# JTAG.net
KiCad netlist of a schematic drawn in Altium Designer
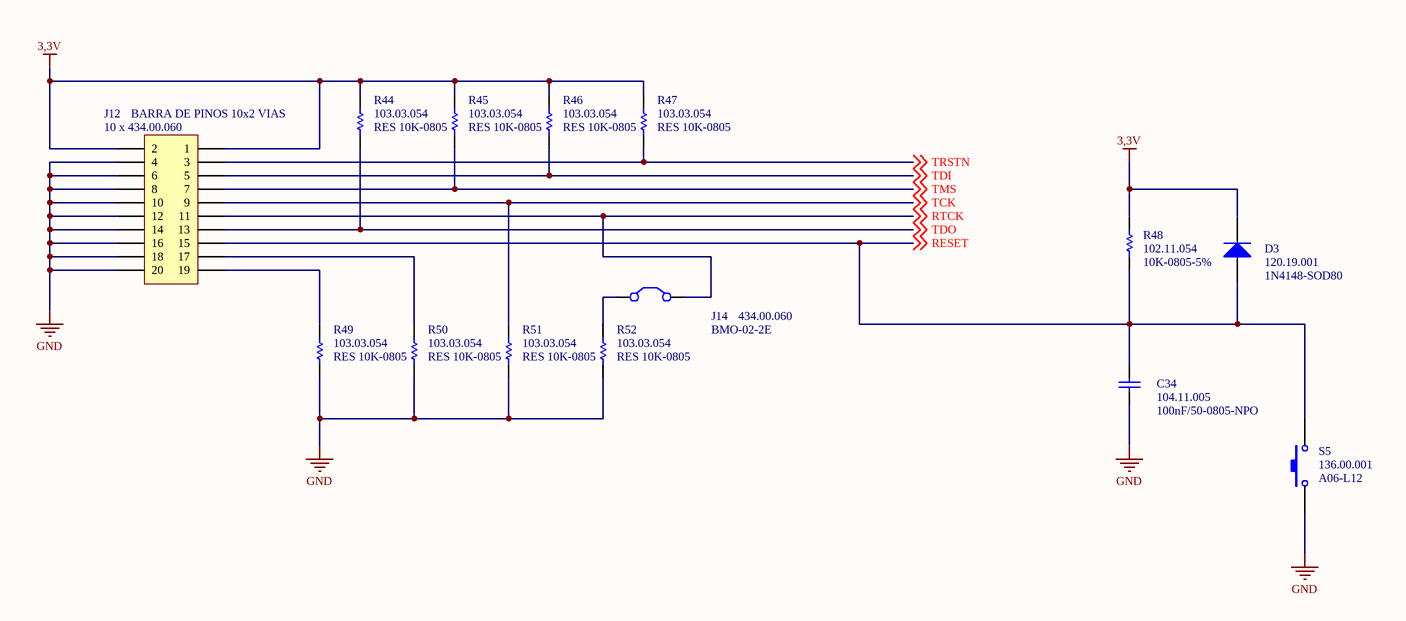
[diagram p0: JTAG.SchDoc]

(export (version "E")
  (design (tool "Eeschema 10.0.6"))
  (components
    (comp (ref "C34")
      (value "100nF/50-0805-NPO")
      (footprint "0805-REVISADO ONDA")
      (fields (field (name "ERP") "104.11.005"))
      (libsource (lib "AquinoLib") (part "100nF/50-0805-NPO"))
    )
    (comp (ref "D3")
      (value "1N4148-SOD80")
      (footprint "MINIMLEF/SOD80 - REVISADO ONDA")
      (fields (field (name "ERP") "120.19.001"))
      (libsource (lib "AquinoLib") (part "1N4148-SOD80"))
    )
    (comp (ref "J12")
      (value "BARRA DE PINOS 10x2 VIAS")
      (footprint "IDCSC-20")
      (fields (field (name "ERP") "10 x 434.00.060"))
      (libsource (lib "ChaveDigital") (part "HEADER 10x2"))
    )
    (comp (ref "J14")
      (value "BMO-02-2E")
      (footprint "JUMPER100")
      (fields (field (name "ERP") "434.00.060"))
      (libsource (lib "ChaveDigital") (part "BARRA DE PINOS"))
    )
    (comp (ref "R44")
      (value "RES 10K-0805")
      (footprint "0805-REVISADO ONDA")
      (fields (field (name "ERP") "103.03.054"))
      (libsource (lib "ChaveDigital") (part "RES 10K-0805"))
    )
    (comp (ref "R45")
      (value "RES 10K-0805")
      (footprint "0805-REVISADO ONDA")
      (fields (field (name "ERP") "103.03.054"))
      (libsource (lib "ChaveDigital") (part "RES 10K-0805"))
    )
    (comp (ref "R46")
      (value "RES 10K-0805")
      (footprint "0805-REVISADO ONDA")
      (fields (field (name "ERP") "103.03.054"))
      (libsource (lib "ChaveDigital") (part "RES 10K-0805"))
    )
    (comp (ref "R47")
      (value "RES 10K-0805")
      (footprint "0805-REVISADO ONDA")
      (fields (field (name "ERP") "103.03.054"))
      (libsource (lib "ChaveDigital") (part "RES 10K-0805"))
    )
    (comp (ref "R48")
      (value "10K-0805-5%")
      (footprint "0805-REVISADO ONDA")
      (fields (field (name "ERP") "102.11.054"))
      (libsource (lib "AquinoLib") (part "10K-0805-5%"))
    )
    (comp (ref "R49")
      (value "RES 10K-0805")
      (footprint "0805-REVISADO ONDA")
      (fields (field (name "ERP") "103.03.054"))
      (libsource (lib "ChaveDigital") (part "RES 10K-0805"))
    )
    (comp (ref "R50")
      (value "RES 10K-0805")
      (footprint "0805-REVISADO ONDA")
      (fields (field (name "ERP") "103.03.054"))
      (libsource (lib "ChaveDigital") (part "RES 10K-0805"))
    )
    (comp (ref "R51")
      (value "RES 10K-0805")
      (footprint "0805-REVISADO ONDA")
      (fields (field (name "ERP") "103.03.054"))
      (libsource (lib "ChaveDigital") (part "RES 10K-0805"))
    )
    (comp (ref "R52")
      (value "RES 10K-0805")
      (footprint "0805-REVISADO ONDA")
      (fields (field (name "ERP") "103.03.054"))
      (libsource (lib "ChaveDigital") (part "RES 10K-0805"))
    )
    (comp (ref "S5")
      (value "A06-L12")
      (footprint "chave tactil nova")
      (fields (field (name "ERP") "136.00.001"))
      (libsource (lib "ChaveDigital3") (part "A06-L12"))
    )
  )
  (nets
    (net (code "1") (name "3,3V") (class "Default")
      (node (ref "D3") (pin "2") (pinfunction "2_2") (pintype "passive"))
      (node (ref "J12") (pin "1") (pinfunction "1_1") (pintype "passive"))
      (node (ref "J12") (pin "2") (pinfunction "2_2") (pintype "passive"))
      (node (ref "R44") (pin "1") (pinfunction "1_1") (pintype "passive"))
      (node (ref "R45") (pin "1") (pinfunction "1_1") (pintype "passive"))
      (node (ref "R46") (pin "1") (pinfunction "1_1") (pintype "passive"))
      (node (ref "R47") (pin "1") (pinfunction "1_1") (pintype "passive"))
      (node (ref "R48") (pin "2") (pinfunction "2_2") (pintype "passive"))
    )
    (net (code "2") (name "GND") (class "Default")
      (node (ref "C34") (pin "1") (pinfunction "1_1") (pintype "passive"))
      (node (ref "J12") (pin "10") (pinfunction "10_10") (pintype "passive"))
      (node (ref "J12") (pin "12") (pinfunction "12_12") (pintype "passive"))
      (node (ref "J12") (pin "14") (pinfunction "14_14") (pintype "passive"))
      (node (ref "J12") (pin "16") (pinfunction "16_16") (pintype "passive"))
      (node (ref "J12") (pin "18") (pinfunction "18_18") (pintype "passive"))
      (node (ref "J12") (pin "20") (pinfunction "20_20") (pintype "passive"))
      (node (ref "J12") (pin "4") (pinfunction "4_4") (pintype "passive"))
      (node (ref "J12") (pin "6") (pinfunction "6_6") (pintype "passive"))
      (node (ref "J12") (pin "8") (pinfunction "8_8") (pintype "passive"))
      (node (ref "R49") (pin "2") (pinfunction "2_2") (pintype "passive"))
      (node (ref "R50") (pin "2") (pinfunction "2_2") (pintype "passive"))
      (node (ref "R51") (pin "2") (pinfunction "2_2") (pintype "passive"))
      (node (ref "R52") (pin "2") (pinfunction "2_2") (pintype "passive"))
      (node (ref "S5") (pin "1") (pinfunction "1_1") (pintype "passive"))
    )
    (net (code "3") (name "Net-(J12-Pad17)") (class "Default")
      (node (ref "J12") (pin "17") (pinfunction "17_17") (pintype "passive"))
      (node (ref "R50") (pin "1") (pinfunction "1_1") (pintype "passive"))
    )
    (net (code "4") (name "Net-(J12-Pad19)") (class "Default")
      (node (ref "J12") (pin "19") (pinfunction "19_19") (pintype "passive"))
      (node (ref "R49") (pin "1") (pinfunction "1_1") (pintype "passive"))
    )
    (net (code "5") (name "Net-(J14-C1)") (class "Default")
      (node (ref "J14") (pin "1") (pinfunction "C1_1") (pintype "passive"))
      (node (ref "R52") (pin "1") (pinfunction "1_1") (pintype "passive"))
    )
    (net (code "6") (name "RESET") (class "Default")
      (node (ref "C34") (pin "2") (pinfunction "2_2") (pintype "passive"))
      (node (ref "D3") (pin "1") (pinfunction "1_1") (pintype "passive"))
      (node (ref "J12") (pin "15") (pinfunction "15_15") (pintype "passive"))
      (node (ref "R48") (pin "1") (pinfunction "1_1") (pintype "passive"))
      (node (ref "S5") (pin "2") (pinfunction "2_2") (pintype "passive"))
    )
    (net (code "7") (name "RTCK") (class "Default")
      (node (ref "J12") (pin "11") (pinfunction "11_11") (pintype "passive"))
      (node (ref "J14") (pin "2") (pinfunction "C2_2") (pintype "passive"))
    )
    (net (code "8") (name "TCK") (class "Default")
      (node (ref "J12") (pin "9") (pinfunction "9_9") (pintype "passive"))
      (node (ref "R51") (pin "1") (pinfunction "1_1") (pintype "passive"))
    )
    (net (code "9") (name "TDI") (class "Default")
      (node (ref "J12") (pin "5") (pinfunction "5_5") (pintype "passive"))
      (node (ref "R46") (pin "2") (pinfunction "2_2") (pintype "passive"))
    )
    (net (code "10") (name "TDO") (class "Default")
      (node (ref "J12") (pin "13") (pinfunction "13_13") (pintype "passive"))
      (node (ref "R44") (pin "2") (pinfunction "2_2") (pintype "passive"))
    )
    (net (code "11") (name "TMS") (class "Default")
      (node (ref "J12") (pin "7") (pinfunction "7_7") (pintype "passive"))
      (node (ref "R45") (pin "2") (pinfunction "2_2") (pintype "passive"))
    )
    (net (code "12") (name "TRSTN") (class "Default")
      (node (ref "J12") (pin "3") (pinfunction "3_3") (pintype "passive"))
      (node (ref "R47") (pin "2") (pinfunction "2_2") (pintype "passive"))
    )
  )
)
